# Leds.net
KiCad netlist of a schematic drawn in Altium Designer
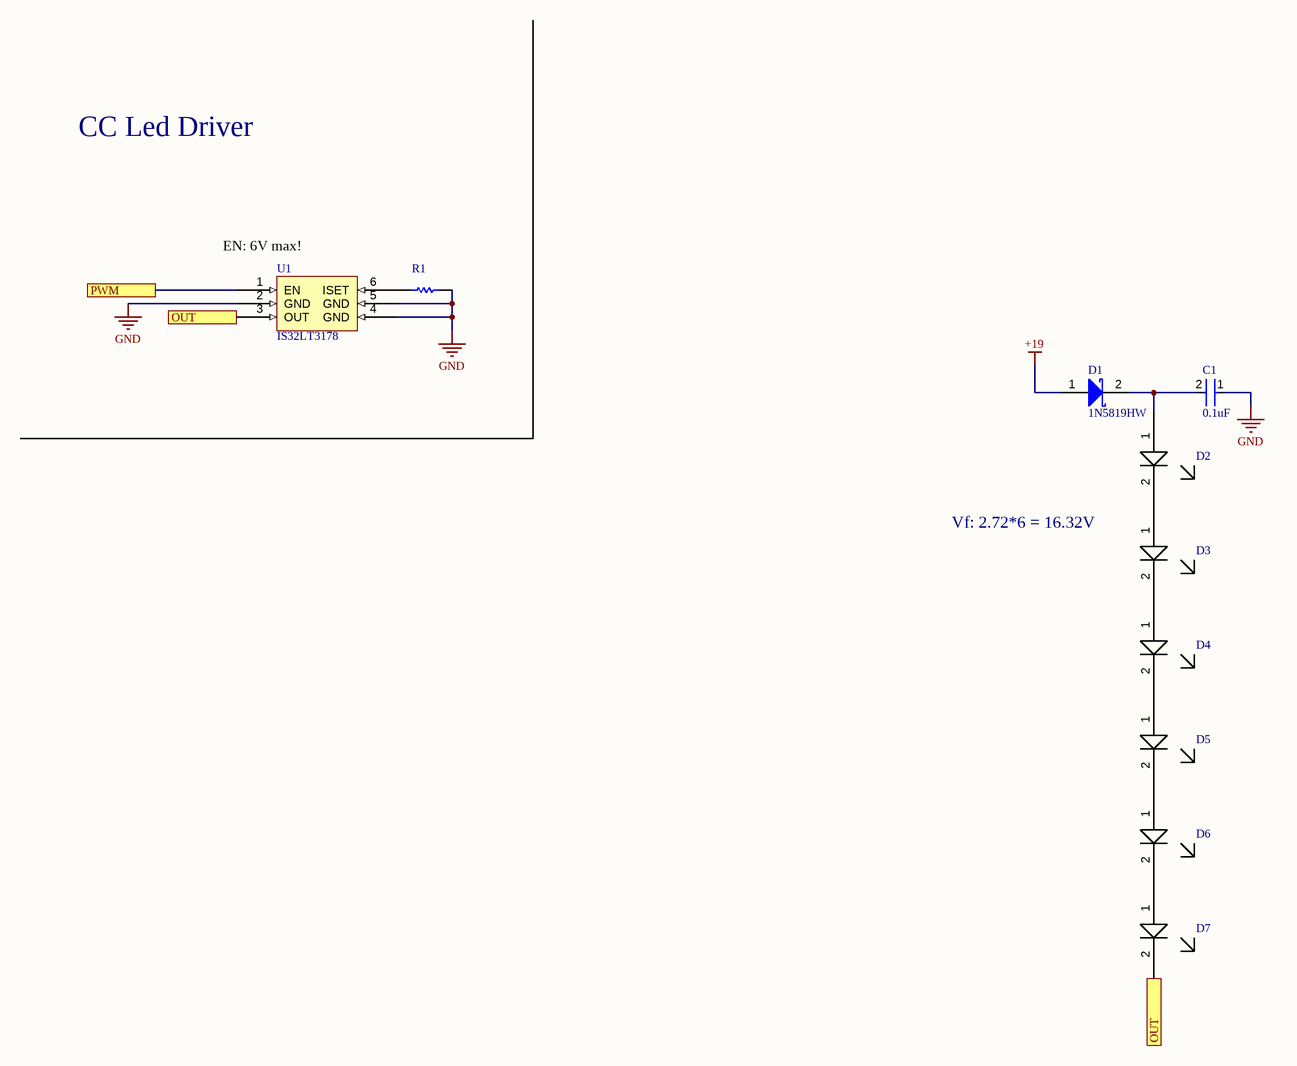
[diagram p0: Leds.SchDoc]

(export (version "E")
  (design (tool "Eeschema 10.0.6"))
  (components
    (comp (ref "C1")
      (value "0.1uF")
      (footprint "FP-0603-L_1_6_0_15-W_0_81-IPC_A")
      (fields (field (name "VOLTAGE") "50V") (field (name "TOLERANCE") "10%"))
      (libsource (lib "Altium Content Vault") (part "02cd4be3c70576c341d710602a673aa"))
    )
    (comp (ref "D1")
      (value "1N5819HW")
      (footprint "DIOD-SOD-123-2_V")
      (fields (field (name "PARTNUMBER") "1N5819HW-7-F") (field (name "MANUFACTURER") "Diodes Inc"))
      (libsource (lib "Altium Content Vault") (part "DIOD-DSKY-A1K2-2"))
    )
    (comp (ref "D2")
      (value "S1W0-2835508003")
      (footprint "S1W0-2835508003")
      (description "LED, Cool 5000K 2.72V 65mA 120° 1411 (3528 Metric)")
      (libsource (lib "jcsb1994_Light") (part "S1W0-2835508003"))
    )
    (comp (ref "D3")
      (value "S1W0-2835508003")
      (footprint "S1W0-2835508003")
      (description "LED, Cool 5000K 2.72V 65mA 120° 1411 (3528 Metric)")
      (libsource (lib "jcsb1994_Light") (part "S1W0-2835508003"))
    )
    (comp (ref "D4")
      (value "S1W0-2835508003")
      (footprint "S1W0-2835508003")
      (description "LED, Cool 5000K 2.72V 65mA 120° 1411 (3528 Metric)")
      (libsource (lib "jcsb1994_Light") (part "S1W0-2835508003"))
    )
    (comp (ref "D5")
      (value "S1W0-2835508003")
      (footprint "S1W0-2835508003")
      (description "LED, Cool 5000K 2.72V 65mA 120° 1411 (3528 Metric)")
      (libsource (lib "jcsb1994_Light") (part "S1W0-2835508003"))
    )
    (comp (ref "D6")
      (value "S1W0-2835508003")
      (footprint "S1W0-2835508003")
      (description "LED, Cool 5000K 2.72V 65mA 120° 1411 (3528 Metric)")
      (libsource (lib "jcsb1994_Light") (part "S1W0-2835508003"))
    )
    (comp (ref "D7")
      (value "S1W0-2835508003")
      (footprint "S1W0-2835508003")
      (description "LED, Cool 5000K 2.72V 65mA 120° 1411 (3528 Metric)")
      (libsource (lib "jcsb1994_Light") (part "S1W0-2835508003"))
    )
    (comp (ref "R1")
      (value "~")
      (footprint "RESC1608X55X25ML10T15")
      (fields (field (name "TOLERANCE") "5%") (field (name "MANUFACTURER") "Yageo"))
      (libsource (lib "Altium Content Vault") (part "RES-2"))
    )
    (comp (ref "U1")
      (value "IS32LT3178")
      (footprint "SOT95P280X135-6N")
      (description "10 TO 150MA CONSTANT CURRENT REG")
      (libsource (lib "jcsb1994_Light") (part "IS32LT3178"))
    )
  )
  (nets
    (net (code "1") (name "+19") (class "Default")
      (node (ref "D1") (pin "1") (pinfunction "A_1") (pintype "passive"))
    )
    (net (code "2") (name "/OUT") (class "Default")
      (node (ref "D7") (pin "2") (pinfunction "C_2") (pintype "passive"))
      (node (ref "U1") (pin "3") (pinfunction "OUT_3") (pintype "input"))
    )
    (net (code "3") (name "/PWM") (class "Default")
      (node (ref "U1") (pin "1") (pinfunction "EN_1") (pintype "input"))
    )
    (net (code "4") (name "GND") (class "Default")
      (node (ref "C1") (pin "1") (pinfunction "1_1") (pintype "passive"))
      (node (ref "R1") (pin "1") (pinfunction "1_1") (pintype "passive"))
      (node (ref "U1") (pin "2") (pinfunction "GND_2") (pintype "input"))
      (node (ref "U1") (pin "4") (pinfunction "GND_4") (pintype "input"))
      (node (ref "U1") (pin "5") (pinfunction "GND_5") (pintype "input"))
    )
    (net (code "5") (name "Net-(D1-K)") (class "Default")
      (node (ref "C1") (pin "2") (pinfunction "2_2") (pintype "passive"))
      (node (ref "D1") (pin "2") (pinfunction "K_2") (pintype "passive"))
      (node (ref "D2") (pin "1") (pinfunction "A_1") (pintype "passive"))
    )
    (net (code "6") (name "Net-(D2-C)") (class "Default")
      (node (ref "D2") (pin "2") (pinfunction "C_2") (pintype "passive"))
      (node (ref "D3") (pin "1") (pinfunction "A_1") (pintype "passive"))
    )
    (net (code "7") (name "Net-(D3-C)") (class "Default")
      (node (ref "D3") (pin "2") (pinfunction "C_2") (pintype "passive"))
      (node (ref "D4") (pin "1") (pinfunction "A_1") (pintype "passive"))
    )
    (net (code "8") (name "Net-(D4-C)") (class "Default")
      (node (ref "D4") (pin "2") (pinfunction "C_2") (pintype "passive"))
      (node (ref "D5") (pin "1") (pinfunction "A_1") (pintype "passive"))
    )
    (net (code "9") (name "Net-(D5-C)") (class "Default")
      (node (ref "D5") (pin "2") (pinfunction "C_2") (pintype "passive"))
      (node (ref "D6") (pin "1") (pinfunction "A_1") (pintype "passive"))
    )
    (net (code "10") (name "Net-(D6-C)") (class "Default")
      (node (ref "D6") (pin "2") (pinfunction "C_2") (pintype "passive"))
      (node (ref "D7") (pin "1") (pinfunction "A_1") (pintype "passive"))
    )
    (net (code "11") (name "Net-(U1-ISET)") (class "Default")
      (node (ref "R1") (pin "2") (pinfunction "2_2") (pintype "passive"))
      (node (ref "U1") (pin "6") (pinfunction "ISET_6") (pintype "input"))
    )
  )
)
